# Ethernet.net
KiCad netlist of a schematic drawn in Altium Designer
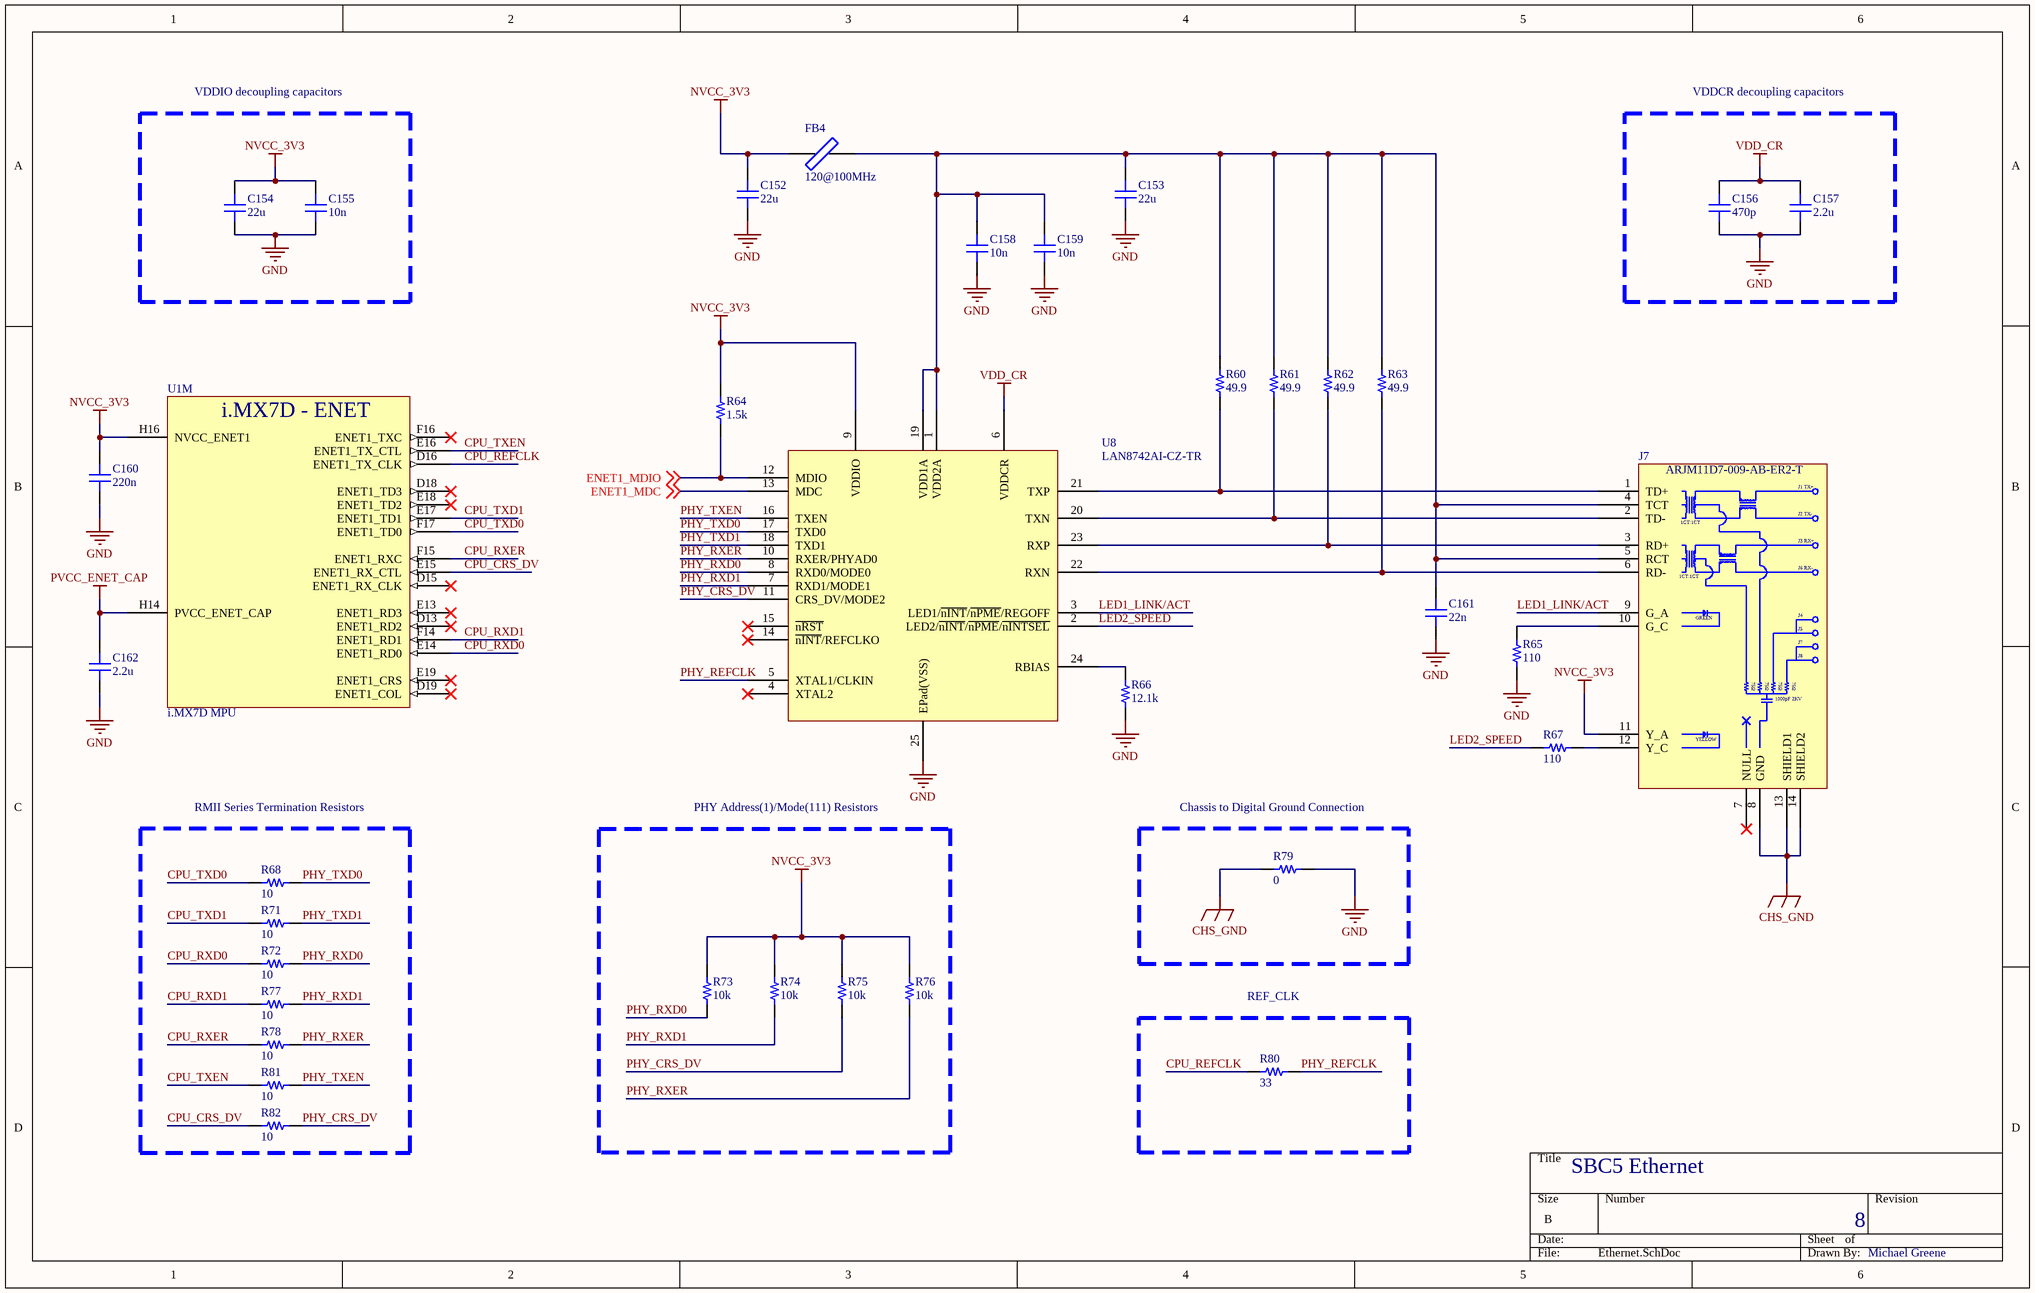
[diagram p0: Ethernet.SchDoc]

(export (version "E")
  (design (tool "Eeschema 10.0.6"))
  (components
    (comp (ref "C152")
      (value "22u")
      (footprint "C0603")
      (description "0603 22 uF 10 V ±20% Tolerance X5R Multilayer Ceramic Chip Capacitor")
      (fields
        (field (name "MANUFACTURER") "Murata")
        (field (name "MANUFACTURER PART NUMBER") "GRM188R61A226ME15D")
      )
      (libsource (lib "SBC5") (part "GRM188R61A226ME15D"))
    )
    (comp (ref "C153")
      (value "22u")
      (footprint "C0603")
      (description "0603 22 uF 10 V ±20% Tolerance X5R Multilayer Ceramic Chip Capacitor")
      (fields
        (field (name "MANUFACTURER") "Murata")
        (field (name "MANUFACTURER PART NUMBER") "GRM188R61A226ME15D")
      )
      (libsource (lib "SBC5") (part "GRM188R61A226ME15D"))
    )
    (comp (ref "C154")
      (value "22u")
      (footprint "C0603")
      (description "0603 22 uF 10 V ±20% Tolerance X5R Multilayer Ceramic Chip Capacitor")
      (fields
        (field (name "MANUFACTURER") "Murata")
        (field (name "MANUFACTURER PART NUMBER") "GRM188R61A226ME15D")
      )
      (libsource (lib "SBC5") (part "GRM188R61A226ME15D"))
    )
    (comp (ref "C155")
      (value "10n")
      (footprint "C0402")
      (fields
        (field (name "MANUFACTURER") "Samsung")
        (field (name "MANUFACTURER PART NUMBER") "CL05B103KO5NNNC")
        (field (name "TOLERANCE") "10%")
      )
      (libsource (lib "SBC5") (part "CL05B103KO5NNNC"))
    )
    (comp (ref "C156")
      (value "470p")
      (footprint "C0402")
      (description "Multilayer Ceramic Capacitors MLCC - SMD/SMT 470pF 50Volts C0G 5%")
      (fields
        (field (name "MANUFACTURER") "Murata")
        (field (name "MANUFACTURER PART NUMBER") "GRM1555C1H471JA01J")
      )
      (libsource (lib "SBC5") (part "GRM1555C1H471JA01J"))
    )
    (comp (ref "C157")
      (value "2.2u")
      (footprint "C0402")
      (description "TAIYO YUDEN         LMK105BJ225MV-F            CERAMIC CAPACITOR, 2.2UF, 10V, X5R, 20%, 0402")
      (fields
        (field (name "MANUFACTURER") "Taiyo Yuden")
        (field (name "MANUFACTURER PART NUMBER") "LMK105BJ225MV-F")
      )
      (libsource (lib "SBC5") (part "LMK105BJ225MV-F"))
    )
    (comp (ref "C158")
      (value "10n")
      (footprint "C0402")
      (fields
        (field (name "MANUFACTURER") "Samsung")
        (field (name "MANUFACTURER PART NUMBER") "CL05B103KO5NNNC")
        (field (name "TOLERANCE") "10%")
      )
      (libsource (lib "SBC5") (part "CL05B103KO5NNNC"))
    )
    (comp (ref "C159")
      (value "10n")
      (footprint "C0402")
      (fields
        (field (name "MANUFACTURER") "Samsung")
        (field (name "MANUFACTURER PART NUMBER") "CL05B103KO5NNNC")
        (field (name "TOLERANCE") "10%")
      )
      (libsource (lib "SBC5") (part "CL05B103KO5NNNC"))
    )
    (comp (ref "C160")
      (value "220n")
      (footprint "C0201")
      (description "Cap Ceramic Monolithic 0.22uF 16VDC 10% SMD Paper T/R")
      (fields
        (field (name "MANUFACTURER") "Murata")
        (field (name "MANUFACTURER PART NUMBER") "GRM033R61C224KE14D")
      )
      (libsource (lib "SBC5") (part "GRM033R61C224KE14D"))
    )
    (comp (ref "C161")
      (value "22n")
      (footprint "C0402")
      (description "Multilayer Ceramic Capacitors MLCC - SMD/SMT 0.022uF 50Volts X7R 10%")
      (fields
        (field (name "MANUFACTURER") "Murata")
        (field (name "MANUFACTURER PART NUMBER") "GRM155R71H223KA12J")
      )
      (libsource (lib "SBC5") (part "GRM155R71H223KA12J"))
    )
    (comp (ref "C162")
      (value "2.2u")
      (footprint "C0402")
      (description "TAIYO YUDEN         LMK105BJ225MV-F            CERAMIC CAPACITOR, 2.2UF, 10V, X5R, 20%, 0402")
      (fields
        (field (name "MANUFACTURER") "Taiyo Yuden")
        (field (name "MANUFACTURER PART NUMBER") "LMK105BJ225MV-F")
      )
      (libsource (lib "SBC5") (part "LMK105BJ225MV-F"))
    )
    (comp (ref "FB4")
      (value "120@100MHz")
      (footprint "L0402")
      (fields
        (field (name "MANUFACTURER") "Murata")
        (field (name "MANUFACTURER PART NUMBER") "BLM15PD121SN1D")
        (field (name "TOLERANCE") "25%")
      )
      (libsource (lib "SBC5") (part "BLM15PD121SN1D"))
    )
    (comp (ref "J7")
      (value "ARJM11D7-009-AB-ER2-T")
      (footprint "ARJM11D7-009-AB-ER2-T")
      (description "Conn RJ-45 F 8 POS 1.27mm Solder RA Thru-Hole 12 Terminal 1 Port T/R")
      (fields (field (name "MANUFACTURER") "Abracon"))
      (libsource (lib "SBC5") (part "ARJM11D7-009-AB-ER2-T"))
    )
    (comp (ref "R60")
      (value "49.9")
      (footprint "R0402")
      (description "RES SMD 49.9 OHM 1% 1/10W 0402")
      (fields
        (field (name "MANUFACTURER") "Vishay BCcomponents")
        (field (name "MANUFACTURER PART NUMBER") "MCS04020C4999FE000")
      )
      (libsource (lib "SBC5") (part "MCS04020C4999FE000"))
    )
    (comp (ref "R61")
      (value "49.9")
      (footprint "R0402")
      (description "RES SMD 49.9 OHM 1% 1/10W 0402")
      (fields
        (field (name "MANUFACTURER") "Vishay BCcomponents")
        (field (name "MANUFACTURER PART NUMBER") "MCS04020C4999FE000")
      )
      (libsource (lib "SBC5") (part "MCS04020C4999FE000"))
    )
    (comp (ref "R62")
      (value "49.9")
      (footprint "R0402")
      (description "RES SMD 49.9 OHM 1% 1/10W 0402")
      (fields
        (field (name "MANUFACTURER") "Vishay BCcomponents")
        (field (name "MANUFACTURER PART NUMBER") "MCS04020C4999FE000")
      )
      (libsource (lib "SBC5") (part "MCS04020C4999FE000"))
    )
    (comp (ref "R63")
      (value "49.9")
      (footprint "R0402")
      (description "RES SMD 49.9 OHM 1% 1/10W 0402")
      (fields
        (field (name "MANUFACTURER") "Vishay BCcomponents")
        (field (name "MANUFACTURER PART NUMBER") "MCS04020C4999FE000")
      )
      (libsource (lib "SBC5") (part "MCS04020C4999FE000"))
    )
    (comp (ref "R64")
      (value "1.5k")
      (footprint "R0402")
      (description "RES 1.5K OHM 1% 1/16W 0402")
      (fields
        (field (name "MANUFACTURER") "Stackpole Electronics")
        (field (name "MANUFACTURER PART NUMBER") "RMCF0402FT1K50")
      )
      (libsource (lib "SBC5") (part "RMCF0402FT1K50"))
    )
    (comp (ref "R65")
      (value "110")
      (footprint "R0402")
      (description "Res Thick Film 0402 110 Ohm 1% 0.063W(1/16W) ±100ppm/C Pad SMD Automotive T/R")
      (fields
        (field (name "MANUFACTURER") "Stackpole Electronics")
        (field (name "MANUFACTURER PART NUMBER") "RMCF0402FT110R")
      )
      (libsource (lib "SBC5") (part "RMCF0402FT110R"))
    )
    (comp (ref "R66")
      (value "12.1k")
      (footprint "R0402")
      (description "Res Thick Film 0402 12.1K Ohm 1% 0.063W ±100ppm/°C Molded SMD Punched Paper T/R")
      (fields
        (field (name "MANUFACTURER") "KOA Speer")
        (field (name "MANUFACTURER PART NUMBER") "RK73H1ETTP1212F")
      )
      (libsource (lib "SBC5") (part "RK73H1ETTP1212F"))
    )
    (comp (ref "R67")
      (value "110")
      (footprint "R0402")
      (description "Res Thick Film 0402 110 Ohm 1% 0.063W(1/16W) ±100ppm/C Pad SMD Automotive T/R")
      (fields
        (field (name "MANUFACTURER") "Stackpole Electronics")
        (field (name "MANUFACTURER PART NUMBER") "RMCF0402FT110R")
      )
      (libsource (lib "SBC5") (part "RMCF0402FT110R"))
    )
    (comp (ref "R68")
      (value "10")
      (footprint "R0402")
      (description "RES 10 OHM 1% 1/16W 0402")
      (fields
        (field (name "MANUFACTURER") "Stackpole Electronics")
        (field (name "MANUFACTURER PART NUMBER") "RMCF0402FT10R0")
      )
      (libsource (lib "SBC5") (part "RMCF0402FT10R0"))
    )
    (comp (ref "R71")
      (value "10")
      (footprint "R0402")
      (description "RES 10 OHM 1% 1/16W 0402")
      (fields
        (field (name "MANUFACTURER") "Stackpole Electronics")
        (field (name "MANUFACTURER PART NUMBER") "RMCF0402FT10R0")
      )
      (libsource (lib "SBC5") (part "RMCF0402FT10R0"))
    )
    (comp (ref "R72")
      (value "10")
      (footprint "R0402")
      (description "RES 10 OHM 1% 1/16W 0402")
      (fields
        (field (name "MANUFACTURER") "Stackpole Electronics")
        (field (name "MANUFACTURER PART NUMBER") "RMCF0402FT10R0")
      )
      (libsource (lib "SBC5") (part "RMCF0402FT10R0"))
    )
    (comp (ref "R73")
      (value "10k")
      (footprint "R0201")
      (description "RES 10K OHM 1% 1/20W 0201")
      (fields
        (field (name "MANUFACTURER") "Stackpole Electronics")
        (field (name "MANUFACTURER PART NUMBER") "RMCF0201FT10K0")
      )
      (libsource (lib "SBC5") (part "RMCF0201FT10K0"))
    )
    (comp (ref "R74")
      (value "10k")
      (footprint "R0201")
      (description "RES 10K OHM 1% 1/20W 0201")
      (fields
        (field (name "MANUFACTURER") "Stackpole Electronics")
        (field (name "MANUFACTURER PART NUMBER") "RMCF0201FT10K0")
      )
      (libsource (lib "SBC5") (part "RMCF0201FT10K0"))
    )
    (comp (ref "R75")
      (value "10k")
      (footprint "R0201")
      (description "RES 10K OHM 1% 1/20W 0201")
      (fields
        (field (name "MANUFACTURER") "Stackpole Electronics")
        (field (name "MANUFACTURER PART NUMBER") "RMCF0201FT10K0")
      )
      (libsource (lib "SBC5") (part "RMCF0201FT10K0"))
    )
    (comp (ref "R76")
      (value "10k")
      (footprint "R0201")
      (description "RES 10K OHM 1% 1/20W 0201")
      (fields
        (field (name "MANUFACTURER") "Stackpole Electronics")
        (field (name "MANUFACTURER PART NUMBER") "RMCF0201FT10K0")
      )
      (libsource (lib "SBC5") (part "RMCF0201FT10K0"))
    )
    (comp (ref "R77")
      (value "10")
      (footprint "R0402")
      (description "RES 10 OHM 1% 1/16W 0402")
      (fields
        (field (name "MANUFACTURER") "Stackpole Electronics")
        (field (name "MANUFACTURER PART NUMBER") "RMCF0402FT10R0")
      )
      (libsource (lib "SBC5") (part "RMCF0402FT10R0"))
    )
    (comp (ref "R78")
      (value "10")
      (footprint "R0402")
      (description "RES 10 OHM 1% 1/16W 0402")
      (fields
        (field (name "MANUFACTURER") "Stackpole Electronics")
        (field (name "MANUFACTURER PART NUMBER") "RMCF0402FT10R0")
      )
      (libsource (lib "SBC5") (part "RMCF0402FT10R0"))
    )
    (comp (ref "R79")
      (value "0")
      (footprint "R1210")
      (description "RES 0.0 OHM 1/2W 1210 SMD")
      (fields
        (field (name "MANUFACTURER") "Stackpole Electronics")
        (field (name "MANUFACTURER PART NUMBER") "RMCF1210ZT0R00")
      )
      (libsource (lib "SBC5") (part "RMCF1210ZT0R00"))
    )
    (comp (ref "R80")
      (value "33")
      (footprint "R0402")
      (description "RES 33 OHM 1% 1/16W 0402")
      (fields
        (field (name "MANUFACTURER") "Stackpole Electronics")
        (field (name "MANUFACTURER PART NUMBER") "RMCF0402FT33R0")
      )
      (libsource (lib "SBC5") (part "RMCF0402FT33R0"))
    )
    (comp (ref "R81")
      (value "10")
      (footprint "R0402")
      (description "RES 10 OHM 1% 1/16W 0402")
      (fields
        (field (name "MANUFACTURER") "Stackpole Electronics")
        (field (name "MANUFACTURER PART NUMBER") "RMCF0402FT10R0")
      )
      (libsource (lib "SBC5") (part "RMCF0402FT10R0"))
    )
    (comp (ref "R82")
      (value "10")
      (footprint "R0402")
      (description "RES 10 OHM 1% 1/16W 0402")
      (fields
        (field (name "MANUFACTURER") "Stackpole Electronics")
        (field (name "MANUFACTURER PART NUMBER") "RMCF0402FT10R0")
      )
      (libsource (lib "SBC5") (part "RMCF0402FT10R0"))
    )
    (comp (ref "U1")
      (value "i.MX7D MPU")
      (footprint "BGA541C75P25X25_1900X1900X140")
      (description "Heterogeneous Multicore Processing Architecture")
      (fields
        (field (name "MANUFACTURER") "NXP Freescale")
        (field (name "MANUFACTURER PART NUMBER") "MCIMX7D2DVM12SD")
      )
      (libsource (lib "SBC5") (part "MCIMX7D2DVM12SD"))
    )
    (comp (ref "U8")
      (value "LAN8742AI-CZ-TR")
      (footprint "LAN8742AI-CZ-TR-ND")
      (fields (field (name "MANUFACTURER") "Microchip"))
      (libsource (lib "SBC5") (part "LAN8742AI-CZ-TR"))
    )
  )
  (nets
    (net (code "1") (name "/CPU_CRS_DV") (class "Default")
      (node (ref "R82") (pin "1") (pinfunction "1_1") (pintype "passive"))
      (node (ref "U1") (pin "E15") (pinfunction "ENET1_RX_CTL_E15") (pintype "input"))
    )
    (net (code "2") (name "/CPU_REFCLK") (class "Default")
      (node (ref "R80") (pin "1") (pinfunction "1_1") (pintype "passive"))
      (node (ref "U1") (pin "D16") (pinfunction "ENET1_TX_CLK_D16") (pintype "output"))
    )
    (net (code "3") (name "/CPU_RXD0") (class "Default")
      (node (ref "R72") (pin "1") (pinfunction "1_1") (pintype "passive"))
      (node (ref "U1") (pin "E14") (pinfunction "ENET1_RD0_E14") (pintype "input"))
    )
    (net (code "4") (name "/CPU_RXD1") (class "Default")
      (node (ref "R77") (pin "1") (pinfunction "1_1") (pintype "passive"))
      (node (ref "U1") (pin "F14") (pinfunction "ENET1_RD1_F14") (pintype "input"))
    )
    (net (code "5") (name "/CPU_RXER") (class "Default")
      (node (ref "R78") (pin "1") (pinfunction "1_1") (pintype "passive"))
      (node (ref "U1") (pin "F15") (pinfunction "ENET1_RXC_F15") (pintype "input"))
    )
    (net (code "6") (name "/CPU_TXD0") (class "Default")
      (node (ref "R68") (pin "1") (pinfunction "1_1") (pintype "passive"))
      (node (ref "U1") (pin "F17") (pinfunction "ENET1_TD0_F17") (pintype "output"))
    )
    (net (code "7") (name "/CPU_TXD1") (class "Default")
      (node (ref "R71") (pin "1") (pinfunction "1_1") (pintype "passive"))
      (node (ref "U1") (pin "E17") (pinfunction "ENET1_TD1_E17") (pintype "output"))
    )
    (net (code "8") (name "/CPU_TXEN") (class "Default")
      (node (ref "R81") (pin "1") (pinfunction "1_1") (pintype "passive"))
      (node (ref "U1") (pin "E16") (pinfunction "ENET1_TX_CTL_E16") (pintype "output"))
    )
    (net (code "9") (name "/LED1_LINK{slash}ACT") (class "Default")
      (node (ref "J7") (pin "9") (pinfunction "G_A_9") (pintype "passive"))
      (node (ref "U8") (pin "3") (pinfunction "LED1/~{nINT}/~{nPME}/REGOFF_3") (pintype "passive"))
    )
    (net (code "10") (name "/LED2_SPEED") (class "Default")
      (node (ref "R67") (pin "1") (pinfunction "1_1") (pintype "passive"))
      (node (ref "U8") (pin "2") (pinfunction "LED2/~{nINT}/~{nPME}/~{nINTSEL}_2") (pintype "passive"))
    )
    (net (code "11") (name "/PHY_CRS_DV") (class "Default")
      (node (ref "R75") (pin "1") (pinfunction "1_1") (pintype "passive"))
      (node (ref "R82") (pin "2") (pinfunction "2_2") (pintype "passive"))
      (node (ref "U8") (pin "11") (pinfunction "CRS_DV/MODE2_11") (pintype "passive"))
    )
    (net (code "12") (name "/PHY_REFCLK") (class "Default")
      (node (ref "R80") (pin "2") (pinfunction "2_2") (pintype "passive"))
      (node (ref "U8") (pin "5") (pinfunction "XTAL1/CLKIN_5") (pintype "passive"))
    )
    (net (code "13") (name "/PHY_RXD0") (class "Default")
      (node (ref "R72") (pin "2") (pinfunction "2_2") (pintype "passive"))
      (node (ref "R73") (pin "1") (pinfunction "1_1") (pintype "passive"))
      (node (ref "U8") (pin "8") (pinfunction "RXD0/MODE0_8") (pintype "passive"))
    )
    (net (code "14") (name "/PHY_RXD1") (class "Default")
      (node (ref "R74") (pin "1") (pinfunction "1_1") (pintype "passive"))
      (node (ref "R77") (pin "2") (pinfunction "2_2") (pintype "passive"))
      (node (ref "U8") (pin "7") (pinfunction "RXD1/MODE1_7") (pintype "passive"))
    )
    (net (code "15") (name "/PHY_RXER") (class "Default")
      (node (ref "R76") (pin "1") (pinfunction "1_1") (pintype "passive"))
      (node (ref "R78") (pin "2") (pinfunction "2_2") (pintype "passive"))
      (node (ref "U8") (pin "10") (pinfunction "RXER/PHYAD0_10") (pintype "passive"))
    )
    (net (code "16") (name "/PHY_TXD0") (class "Default")
      (node (ref "R68") (pin "2") (pinfunction "2_2") (pintype "passive"))
      (node (ref "U8") (pin "17") (pinfunction "TXD0_17") (pintype "passive"))
    )
    (net (code "17") (name "/PHY_TXD1") (class "Default")
      (node (ref "R71") (pin "2") (pinfunction "2_2") (pintype "passive"))
      (node (ref "U8") (pin "18") (pinfunction "TXD1_18") (pintype "passive"))
    )
    (net (code "18") (name "/PHY_TXEN") (class "Default")
      (node (ref "R81") (pin "2") (pinfunction "2_2") (pintype "passive"))
      (node (ref "U8") (pin "16") (pinfunction "TXEN_16") (pintype "passive"))
    )
    (net (code "19") (name "CHS_GND") (class "Default")
      (node (ref "J7") (pin "13") (pinfunction "SHIELD1_13") (pintype "passive"))
      (node (ref "J7") (pin "14") (pinfunction "SHIELD2_14") (pintype "passive"))
      (node (ref "J7") (pin "8") (pinfunction "GND_8") (pintype "passive"))
      (node (ref "R79") (pin "1") (pinfunction "1_1") (pintype "passive"))
    )
    (net (code "20") (name "ENET1_MDC") (class "Default")
      (node (ref "U8") (pin "13") (pinfunction "MDC_13") (pintype "passive"))
    )
    (net (code "21") (name "ENET1_MDIO") (class "Default")
      (node (ref "R64") (pin "1") (pinfunction "1_1") (pintype "passive"))
      (node (ref "U8") (pin "12") (pinfunction "MDIO_12") (pintype "passive"))
    )
    (net (code "22") (name "GND") (class "Default")
      (node (ref "C152") (pin "1") (pinfunction "1_1") (pintype "passive"))
      (node (ref "C153") (pin "1") (pinfunction "1_1") (pintype "passive"))
      (node (ref "C154") (pin "1") (pinfunction "1_1") (pintype "passive"))
      (node (ref "C155") (pin "1") (pinfunction "1_1") (pintype "passive"))
      (node (ref "C156") (pin "1") (pinfunction "1_1") (pintype "passive"))
      (node (ref "C157") (pin "1") (pinfunction "1_1") (pintype "passive"))
      (node (ref "C158") (pin "2") (pinfunction "2_2") (pintype "passive"))
      (node (ref "C159") (pin "1") (pinfunction "1_1") (pintype "passive"))
      (node (ref "C160") (pin "1") (pinfunction "1_1") (pintype "passive"))
      (node (ref "C161") (pin "1") (pinfunction "1_1") (pintype "passive"))
      (node (ref "C162") (pin "1") (pinfunction "1_1") (pintype "passive"))
      (node (ref "R65") (pin "1") (pinfunction "1_1") (pintype "passive"))
      (node (ref "R66") (pin "1") (pinfunction "1_1") (pintype "passive"))
      (node (ref "R79") (pin "2") (pinfunction "2_2") (pintype "passive"))
      (node (ref "U8") (pin "25") (pinfunction "EPad(VSS)_25") (pintype "passive"))
    )
    (net (code "23") (name "NVCC_3V3") (class "Default")
      (node (ref "C152") (pin "2") (pinfunction "2_2") (pintype "passive"))
      (node (ref "C154") (pin "2") (pinfunction "2_2") (pintype "passive"))
      (node (ref "C155") (pin "2") (pinfunction "2_2") (pintype "passive"))
      (node (ref "C160") (pin "2") (pinfunction "2_2") (pintype "passive"))
      (node (ref "FB4") (pin "1") (pinfunction "1_1") (pintype "passive"))
      (node (ref "J7") (pin "11") (pinfunction "Y_A_11") (pintype "passive"))
      (node (ref "R64") (pin "2") (pinfunction "2_2") (pintype "passive"))
      (node (ref "R73") (pin "2") (pinfunction "2_2") (pintype "passive"))
      (node (ref "R74") (pin "2") (pinfunction "2_2") (pintype "passive"))
      (node (ref "R75") (pin "2") (pinfunction "2_2") (pintype "passive"))
      (node (ref "R76") (pin "2") (pinfunction "2_2") (pintype "passive"))
      (node (ref "U1") (pin "H16") (pinfunction "NVCC_ENET1_H16") (pintype "power_in"))
      (node (ref "U8") (pin "9") (pinfunction "VDDIO_9") (pintype "passive"))
    )
    (net (code "24") (name "Net-(J7-G_C)") (class "Default")
      (node (ref "J7") (pin "10") (pinfunction "G_C_10") (pintype "passive"))
      (node (ref "R65") (pin "2") (pinfunction "2_2") (pintype "passive"))
    )
    (net (code "25") (name "Net-(J7-RCT)") (class "Default")
      (node (ref "C153") (pin "2") (pinfunction "2_2") (pintype "passive"))
      (node (ref "C158") (pin "1") (pinfunction "1_1") (pintype "passive"))
      (node (ref "C159") (pin "2") (pinfunction "2_2") (pintype "passive"))
      (node (ref "C161") (pin "2") (pinfunction "2_2") (pintype "passive"))
      (node (ref "FB4") (pin "2") (pinfunction "2_2") (pintype "passive"))
      (node (ref "J7") (pin "4") (pinfunction "TCT_4") (pintype "passive"))
      (node (ref "J7") (pin "5") (pinfunction "RCT_5") (pintype "passive"))
      (node (ref "R60") (pin "2") (pinfunction "2_2") (pintype "passive"))
      (node (ref "R61") (pin "2") (pinfunction "2_2") (pintype "passive"))
      (node (ref "R62") (pin "2") (pinfunction "2_2") (pintype "passive"))
      (node (ref "R63") (pin "2") (pinfunction "2_2") (pintype "passive"))
      (node (ref "U8") (pin "1") (pinfunction "VDD2A_1") (pintype "passive"))
      (node (ref "U8") (pin "19") (pinfunction "VDD1A_19") (pintype "passive"))
    )
    (net (code "26") (name "Net-(J7-RD+)") (class "Default")
      (node (ref "J7") (pin "3") (pinfunction "RD+_3") (pintype "passive"))
      (node (ref "R62") (pin "1") (pinfunction "1_1") (pintype "passive"))
      (node (ref "U8") (pin "23") (pinfunction "RXP_23") (pintype "passive"))
    )
    (net (code "27") (name "Net-(J7-RD-)") (class "Default")
      (node (ref "J7") (pin "6") (pinfunction "RD-_6") (pintype "passive"))
      (node (ref "R63") (pin "1") (pinfunction "1_1") (pintype "passive"))
      (node (ref "U8") (pin "22") (pinfunction "RXN_22") (pintype "passive"))
    )
    (net (code "28") (name "Net-(J7-TD+)") (class "Default")
      (node (ref "J7") (pin "1") (pinfunction "TD+_1") (pintype "passive"))
      (node (ref "R60") (pin "1") (pinfunction "1_1") (pintype "passive"))
      (node (ref "U8") (pin "21") (pinfunction "TXP_21") (pintype "passive"))
    )
    (net (code "29") (name "Net-(J7-TD-)") (class "Default")
      (node (ref "J7") (pin "2") (pinfunction "TD-_2") (pintype "passive"))
      (node (ref "R61") (pin "1") (pinfunction "1_1") (pintype "passive"))
      (node (ref "U8") (pin "20") (pinfunction "TXN_20") (pintype "passive"))
    )
    (net (code "30") (name "Net-(J7-Y_C)") (class "Default")
      (node (ref "J7") (pin "12") (pinfunction "Y_C_12") (pintype "passive"))
      (node (ref "R67") (pin "2") (pinfunction "2_2") (pintype "passive"))
    )
    (net (code "31") (name "Net-(U8-RBIAS)") (class "Default")
      (node (ref "R66") (pin "2") (pinfunction "2_2") (pintype "passive"))
      (node (ref "U8") (pin "24") (pinfunction "RBIAS_24") (pintype "passive"))
    )
    (net (code "32") (name "PVCC_ENET_CAP") (class "Default")
      (node (ref "C162") (pin "2") (pinfunction "2_2") (pintype "passive"))
      (node (ref "U1") (pin "H14") (pinfunction "PVCC_ENET_CAP_H14") (pintype "power_in"))
    )
    (net (code "33") (name "VDD_CR") (class "Default")
      (node (ref "C156") (pin "2") (pinfunction "2_2") (pintype "passive"))
      (node (ref "C157") (pin "2") (pinfunction "2_2") (pintype "passive"))
      (node (ref "U8") (pin "6") (pinfunction "VDDCR_6") (pintype "passive"))
    )
    (net (code "34") (name "unconnected-(J7-NULL-Pad7)") (class "Default")
      (node (ref "J7") (pin "7") (pinfunction "NULL_7") (pintype "passive+no_connect"))
    )
    (net (code "35") (name "unconnected-(U1M-ENET1_COL-PadD19)") (class "Default")
      (node (ref "U1") (pin "D19") (pinfunction "ENET1_COL_D19") (pintype "input+no_connect"))
    )
    (net (code "36") (name "unconnected-(U1M-ENET1_CRS-PadE19)") (class "Default")
      (node (ref "U1") (pin "E19") (pinfunction "ENET1_CRS_E19") (pintype "input+no_connect"))
    )
    (net (code "37") (name "unconnected-(U1M-ENET1_RD2-PadD13)") (class "Default")
      (node (ref "U1") (pin "D13") (pinfunction "ENET1_RD2_D13") (pintype "input+no_connect"))
    )
    (net (code "38") (name "unconnected-(U1M-ENET1_RD3-PadE13)") (class "Default")
      (node (ref "U1") (pin "E13") (pinfunction "ENET1_RD3_E13") (pintype "input+no_connect"))
    )
    (net (code "39") (name "unconnected-(U1M-ENET1_RX_CLK-PadD15)") (class "Default")
      (node (ref "U1") (pin "D15") (pinfunction "ENET1_RX_CLK_D15") (pintype "input+no_connect"))
    )
    (net (code "40") (name "unconnected-(U1M-ENET1_TD2-PadE18)") (class "Default")
      (node (ref "U1") (pin "E18") (pinfunction "ENET1_TD2_E18") (pintype "output+no_connect"))
    )
    (net (code "41") (name "unconnected-(U1M-ENET1_TD3-PadD18)") (class "Default")
      (node (ref "U1") (pin "D18") (pinfunction "ENET1_TD3_D18") (pintype "output+no_connect"))
    )
    (net (code "42") (name "unconnected-(U1M-ENET1_TXC-PadF16)") (class "Default")
      (node (ref "U1") (pin "F16") (pinfunction "ENET1_TXC_F16") (pintype "output+no_connect"))
    )
    (net (code "43") (name "unconnected-(U8-XTAL2-Pad4)") (class "Default")
      (node (ref "U8") (pin "4") (pinfunction "XTAL2_4") (pintype "passive+no_connect"))
    )
    (net (code "44") (name "unconnected-(U8-~{nINT}{slash}REFCLKO-Pad14)") (class "Default")
      (node (ref "U8") (pin "14") (pinfunction "~{nINT}/REFCLKO_14") (pintype "passive+no_connect"))
    )
    (net (code "45") (name "unconnected-(U8-~{nRST}-Pad15)") (class "Default")
      (node (ref "U8") (pin "15") (pinfunction "~{nRST}_15") (pintype "passive+no_connect"))
    )
  )
)
